# breakout_da14580.net
KiCad netlist of a schematic drawn in EAGLE
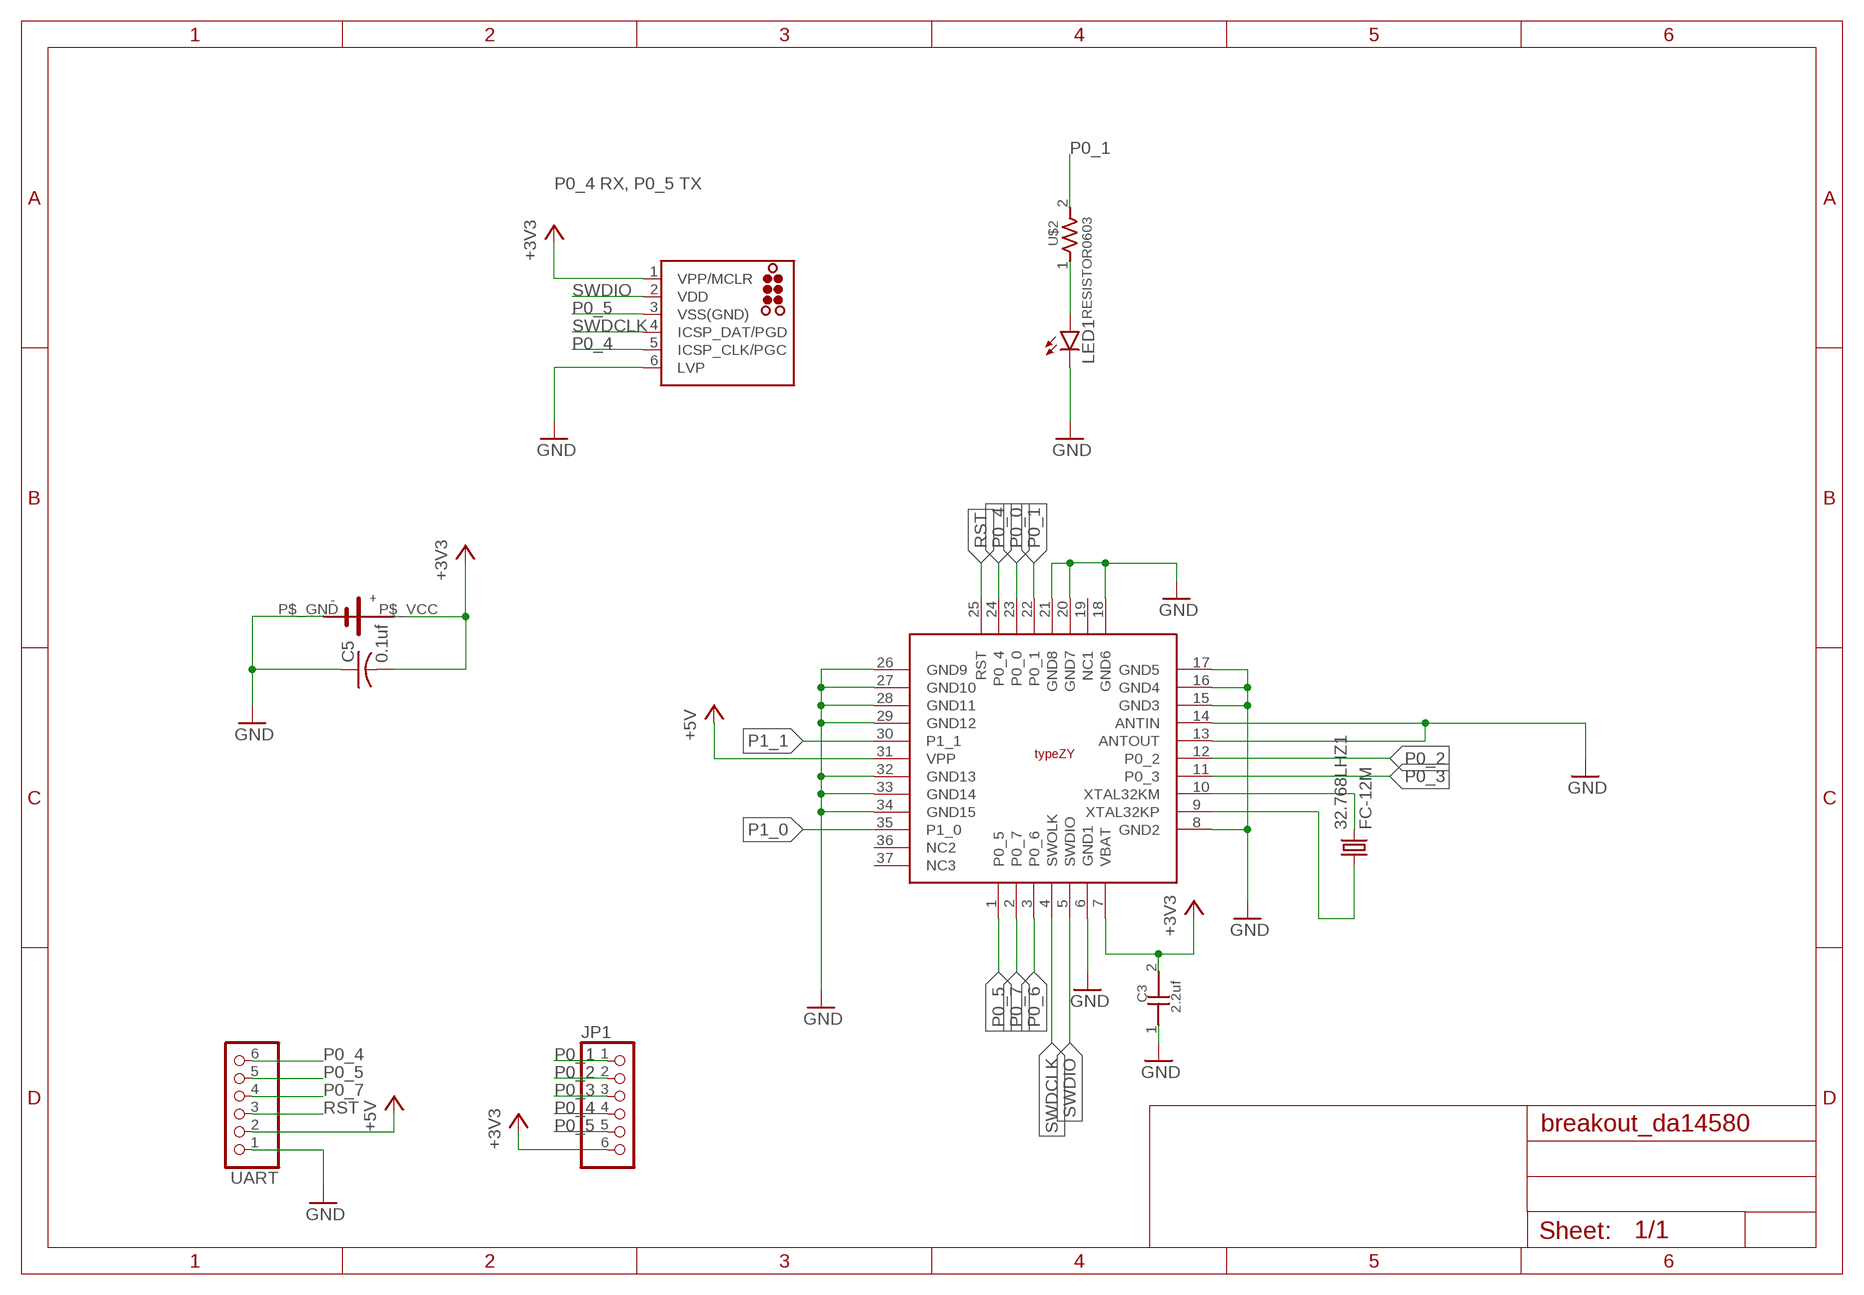
[diagram p0: schematic, sheet 1]

(export (version "E")
  (design (tool "Eeschema 10.0.6"))
  (components
    (comp (ref "32.768LHZ1")
      (value "FC-12M")
      (footprint "eagle-import:FC-12M")
      (libsource (lib "eagle-import") (part "FC-12M"))
    )
    (comp (ref "C3")
      (value "2.2uf")
      (footprint "eagle-import:0603")
      (libsource (lib "eagle-import") (part "CAPACITOR0603"))
    )
    (comp (ref "C5")
      (value "0.1uf")
      (footprint "eagle-import:C0603")
      (libsource (lib "eagle-import") (part "C-USC0603"))
    )
    (comp (ref "J1")
      (value "TC2030-MCP")
      (footprint "eagle-import:TC2030-MCP")
      (libsource (lib "eagle-import") (part "TC2030-MCP"))
    )
    (comp (ref "JP1")
      (value "PINHD-1X6")
      (footprint "eagle-import:1X06")
      (libsource (lib "eagle-import") (part "PINHD-1X6"))
    )
    (comp (ref "LED1")
      (value "LED-EIA0603")
      (footprint "eagle-import:EIA0603-LED")
      (libsource (lib "eagle-import") (part "LED-EIA0603"))
    )
    (comp (ref "U$1")
      (value "MURATA-TYPEZY")
      (footprint "eagle-import:MURATA_TYPEZY")
      (libsource (lib "eagle-import") (part "MURATA-TYPEZY"))
    )
    (comp (ref "U$2")
      (value "RESISTOR0603")
      (footprint "eagle-import:0603")
      (libsource (lib "eagle-import") (part "RESISTOR0603"))
    )
    (comp (ref "U$3")
      (value "SMTU2450-BOTTOM-MINI")
      (footprint "eagle-import:SMTU2450-BOTTOM-MINI")
      (libsource (lib "eagle-import") (part "SMTU2450-BOTTOM-MINI"))
    )
    (comp (ref "UART")
      (value "PINHD-1X6")
      (footprint "eagle-import:1X06")
      (libsource (lib "eagle-import") (part "PINHD-1X6"))
    )
  )
  (nets
    (net (code "1") (name "+3V3") (class "Default")
      (node (ref "C3") (pin "2") (pinfunction "2_2") (pintype "passive"))
      (node (ref "C5") (pin "2") (pinfunction "2_2") (pintype "passive"))
      (node (ref "J1") (pin "1") (pinfunction "VPP/MCLR_1") (pintype "passive"))
      (node (ref "JP1") (pin "6") (pinfunction "6_6") (pintype "passive"))
      (node (ref "U$1") (pin "7") (pinfunction "VBAT_7") (pintype "bidirectional"))
      (node (ref "U$3") (pin "P$_VCC") (pinfunction "P$_VCC_P$_VCC") (pintype "bidirectional"))
    )
    (net (code "2") (name "+5V") (class "Default")
      (node (ref "U$1") (pin "31") (pinfunction "VPP_31") (pintype "bidirectional"))
      (node (ref "UART") (pin "2") (pinfunction "2_2") (pintype "passive"))
    )
    (net (code "3") (name "GND") (class "Default")
      (node (ref "C3") (pin "1") (pinfunction "1_1") (pintype "passive"))
      (node (ref "C5") (pin "1") (pinfunction "1_1") (pintype "passive"))
      (node (ref "J1") (pin "6") (pinfunction "LVP_6") (pintype "bidirectional"))
      (node (ref "LED1") (pin "C") (pinfunction "C_C") (pintype "passive"))
      (node (ref "U$1") (pin "13") (pinfunction "ANTOUT_13") (pintype "bidirectional"))
      (node (ref "U$1") (pin "14") (pinfunction "ANTIN_14") (pintype "bidirectional"))
      (node (ref "U$1") (pin "15") (pinfunction "GND3_15") (pintype "bidirectional"))
      (node (ref "U$1") (pin "16") (pinfunction "GND4_16") (pintype "bidirectional"))
      (node (ref "U$1") (pin "17") (pinfunction "GND5_17") (pintype "bidirectional"))
      (node (ref "U$1") (pin "18") (pinfunction "GND6_18") (pintype "bidirectional"))
      (node (ref "U$1") (pin "20") (pinfunction "GND7_20") (pintype "bidirectional"))
      (node (ref "U$1") (pin "21") (pinfunction "GND8_21") (pintype "bidirectional"))
      (node (ref "U$1") (pin "26") (pinfunction "GND9_26") (pintype "bidirectional"))
      (node (ref "U$1") (pin "27") (pinfunction "GND10_27") (pintype "bidirectional"))
      (node (ref "U$1") (pin "28") (pinfunction "GND11_28") (pintype "bidirectional"))
      (node (ref "U$1") (pin "29") (pinfunction "GND12_29") (pintype "bidirectional"))
      (node (ref "U$1") (pin "32") (pinfunction "GND13_32") (pintype "bidirectional"))
      (node (ref "U$1") (pin "33") (pinfunction "GND14_33") (pintype "bidirectional"))
      (node (ref "U$1") (pin "34") (pinfunction "GND15_34") (pintype "bidirectional"))
      (node (ref "U$1") (pin "6") (pinfunction "GND1_6") (pintype "bidirectional"))
      (node (ref "U$1") (pin "8") (pinfunction "GND2_8") (pintype "bidirectional"))
      (node (ref "U$3") (pin "P$_GND") (pinfunction "P$_GND_P$_GND") (pintype "bidirectional"))
      (node (ref "UART") (pin "1") (pinfunction "1_1") (pintype "passive"))
    )
    (net (code "4") (name "Net-(LED1-PadA)") (class "Default")
      (node (ref "LED1") (pin "A") (pinfunction "A_A") (pintype "passive"))
      (node (ref "U$2") (pin "1") (pinfunction "1_1") (pintype "passive"))
    )
    (net (code "5") (name "Net-(U$1-XTAL32KM)") (class "Default")
      (node (ref "32.768LHZ1") (pin "2") (pinfunction "2_2") (pintype "passive"))
      (node (ref "U$1") (pin "10") (pinfunction "XTAL32KM_10") (pintype "bidirectional"))
    )
    (net (code "6") (name "Net-(U$1-XTAL32KP)") (class "Default")
      (node (ref "32.768LHZ1") (pin "1") (pinfunction "1_1") (pintype "passive"))
      (node (ref "U$1") (pin "9") (pinfunction "XTAL32KP_9") (pintype "bidirectional"))
    )
    (net (code "7") (name "P0_0") (class "Default")
      (node (ref "U$1") (pin "23") (pinfunction "P0_0_23") (pintype "bidirectional"))
    )
    (net (code "8") (name "P0_1") (class "Default")
      (node (ref "JP1") (pin "1") (pinfunction "1_1") (pintype "passive"))
      (node (ref "U$1") (pin "22") (pinfunction "P0_1_22") (pintype "bidirectional"))
      (node (ref "U$2") (pin "2") (pinfunction "2_2") (pintype "passive"))
    )
    (net (code "9") (name "P0_2") (class "Default")
      (node (ref "JP1") (pin "2") (pinfunction "2_2") (pintype "passive"))
      (node (ref "U$1") (pin "12") (pinfunction "P0_2_12") (pintype "bidirectional"))
    )
    (net (code "10") (name "P0_3") (class "Default")
      (node (ref "JP1") (pin "3") (pinfunction "3_3") (pintype "passive"))
      (node (ref "U$1") (pin "11") (pinfunction "P0_3_11") (pintype "bidirectional"))
    )
    (net (code "11") (name "P0_4") (class "Default")
      (node (ref "J1") (pin "5") (pinfunction "ICSP_CLK/PGC_5") (pintype "output"))
      (node (ref "JP1") (pin "4") (pinfunction "4_4") (pintype "passive"))
      (node (ref "U$1") (pin "24") (pinfunction "P0_4_24") (pintype "bidirectional"))
      (node (ref "UART") (pin "6") (pinfunction "6_6") (pintype "passive"))
    )
    (net (code "12") (name "P0_5") (class "Default")
      (node (ref "J1") (pin "3") (pinfunction "VSS(GND)_3") (pintype "power_in"))
      (node (ref "JP1") (pin "5") (pinfunction "5_5") (pintype "passive"))
      (node (ref "U$1") (pin "1") (pinfunction "P0_5_1") (pintype "bidirectional"))
      (node (ref "UART") (pin "5") (pinfunction "5_5") (pintype "passive"))
    )
    (net (code "13") (name "P0_6") (class "Default")
      (node (ref "U$1") (pin "3") (pinfunction "P0_6_3") (pintype "bidirectional"))
    )
    (net (code "14") (name "P0_7") (class "Default")
      (node (ref "U$1") (pin "2") (pinfunction "P0_7_2") (pintype "bidirectional"))
      (node (ref "UART") (pin "4") (pinfunction "4_4") (pintype "passive"))
    )
    (net (code "15") (name "P1_0") (class "Default")
      (node (ref "U$1") (pin "35") (pinfunction "P1_0_35") (pintype "bidirectional"))
    )
    (net (code "16") (name "P1_1") (class "Default")
      (node (ref "U$1") (pin "30") (pinfunction "P1_1_30") (pintype "bidirectional"))
    )
    (net (code "17") (name "RST") (class "Default")
      (node (ref "U$1") (pin "25") (pinfunction "RST_25") (pintype "bidirectional"))
      (node (ref "UART") (pin "3") (pinfunction "3_3") (pintype "passive"))
    )
    (net (code "18") (name "SWDCLK") (class "Default")
      (node (ref "J1") (pin "4") (pinfunction "ICSP_DAT/PGD_4") (pintype "bidirectional"))
      (node (ref "U$1") (pin "4") (pinfunction "SWOLK_4") (pintype "bidirectional"))
    )
    (net (code "19") (name "SWDIO") (class "Default")
      (node (ref "J1") (pin "2") (pinfunction "VDD_2") (pintype "power_in"))
      (node (ref "U$1") (pin "5") (pinfunction "SWDIO_5") (pintype "bidirectional"))
    )
    (net (code "20") (name "unconnected-(U$1-NC1-Pad19)") (class "Default")
      (node (ref "U$1") (pin "19") (pinfunction "NC1_19") (pintype "bidirectional"))
    )
    (net (code "21") (name "unconnected-(U$1-NC2-Pad36)") (class "Default")
      (node (ref "U$1") (pin "36") (pinfunction "NC2_36") (pintype "bidirectional"))
    )
    (net (code "22") (name "unconnected-(U$1-NC3-Pad37)") (class "Default")
      (node (ref "U$1") (pin "37") (pinfunction "NC3_37") (pintype "bidirectional"))
    )
  )
)
